# SCH_Tanbre_v2_2026-05-30.net
KiCad netlist of a schematic drawn in EasyEDA
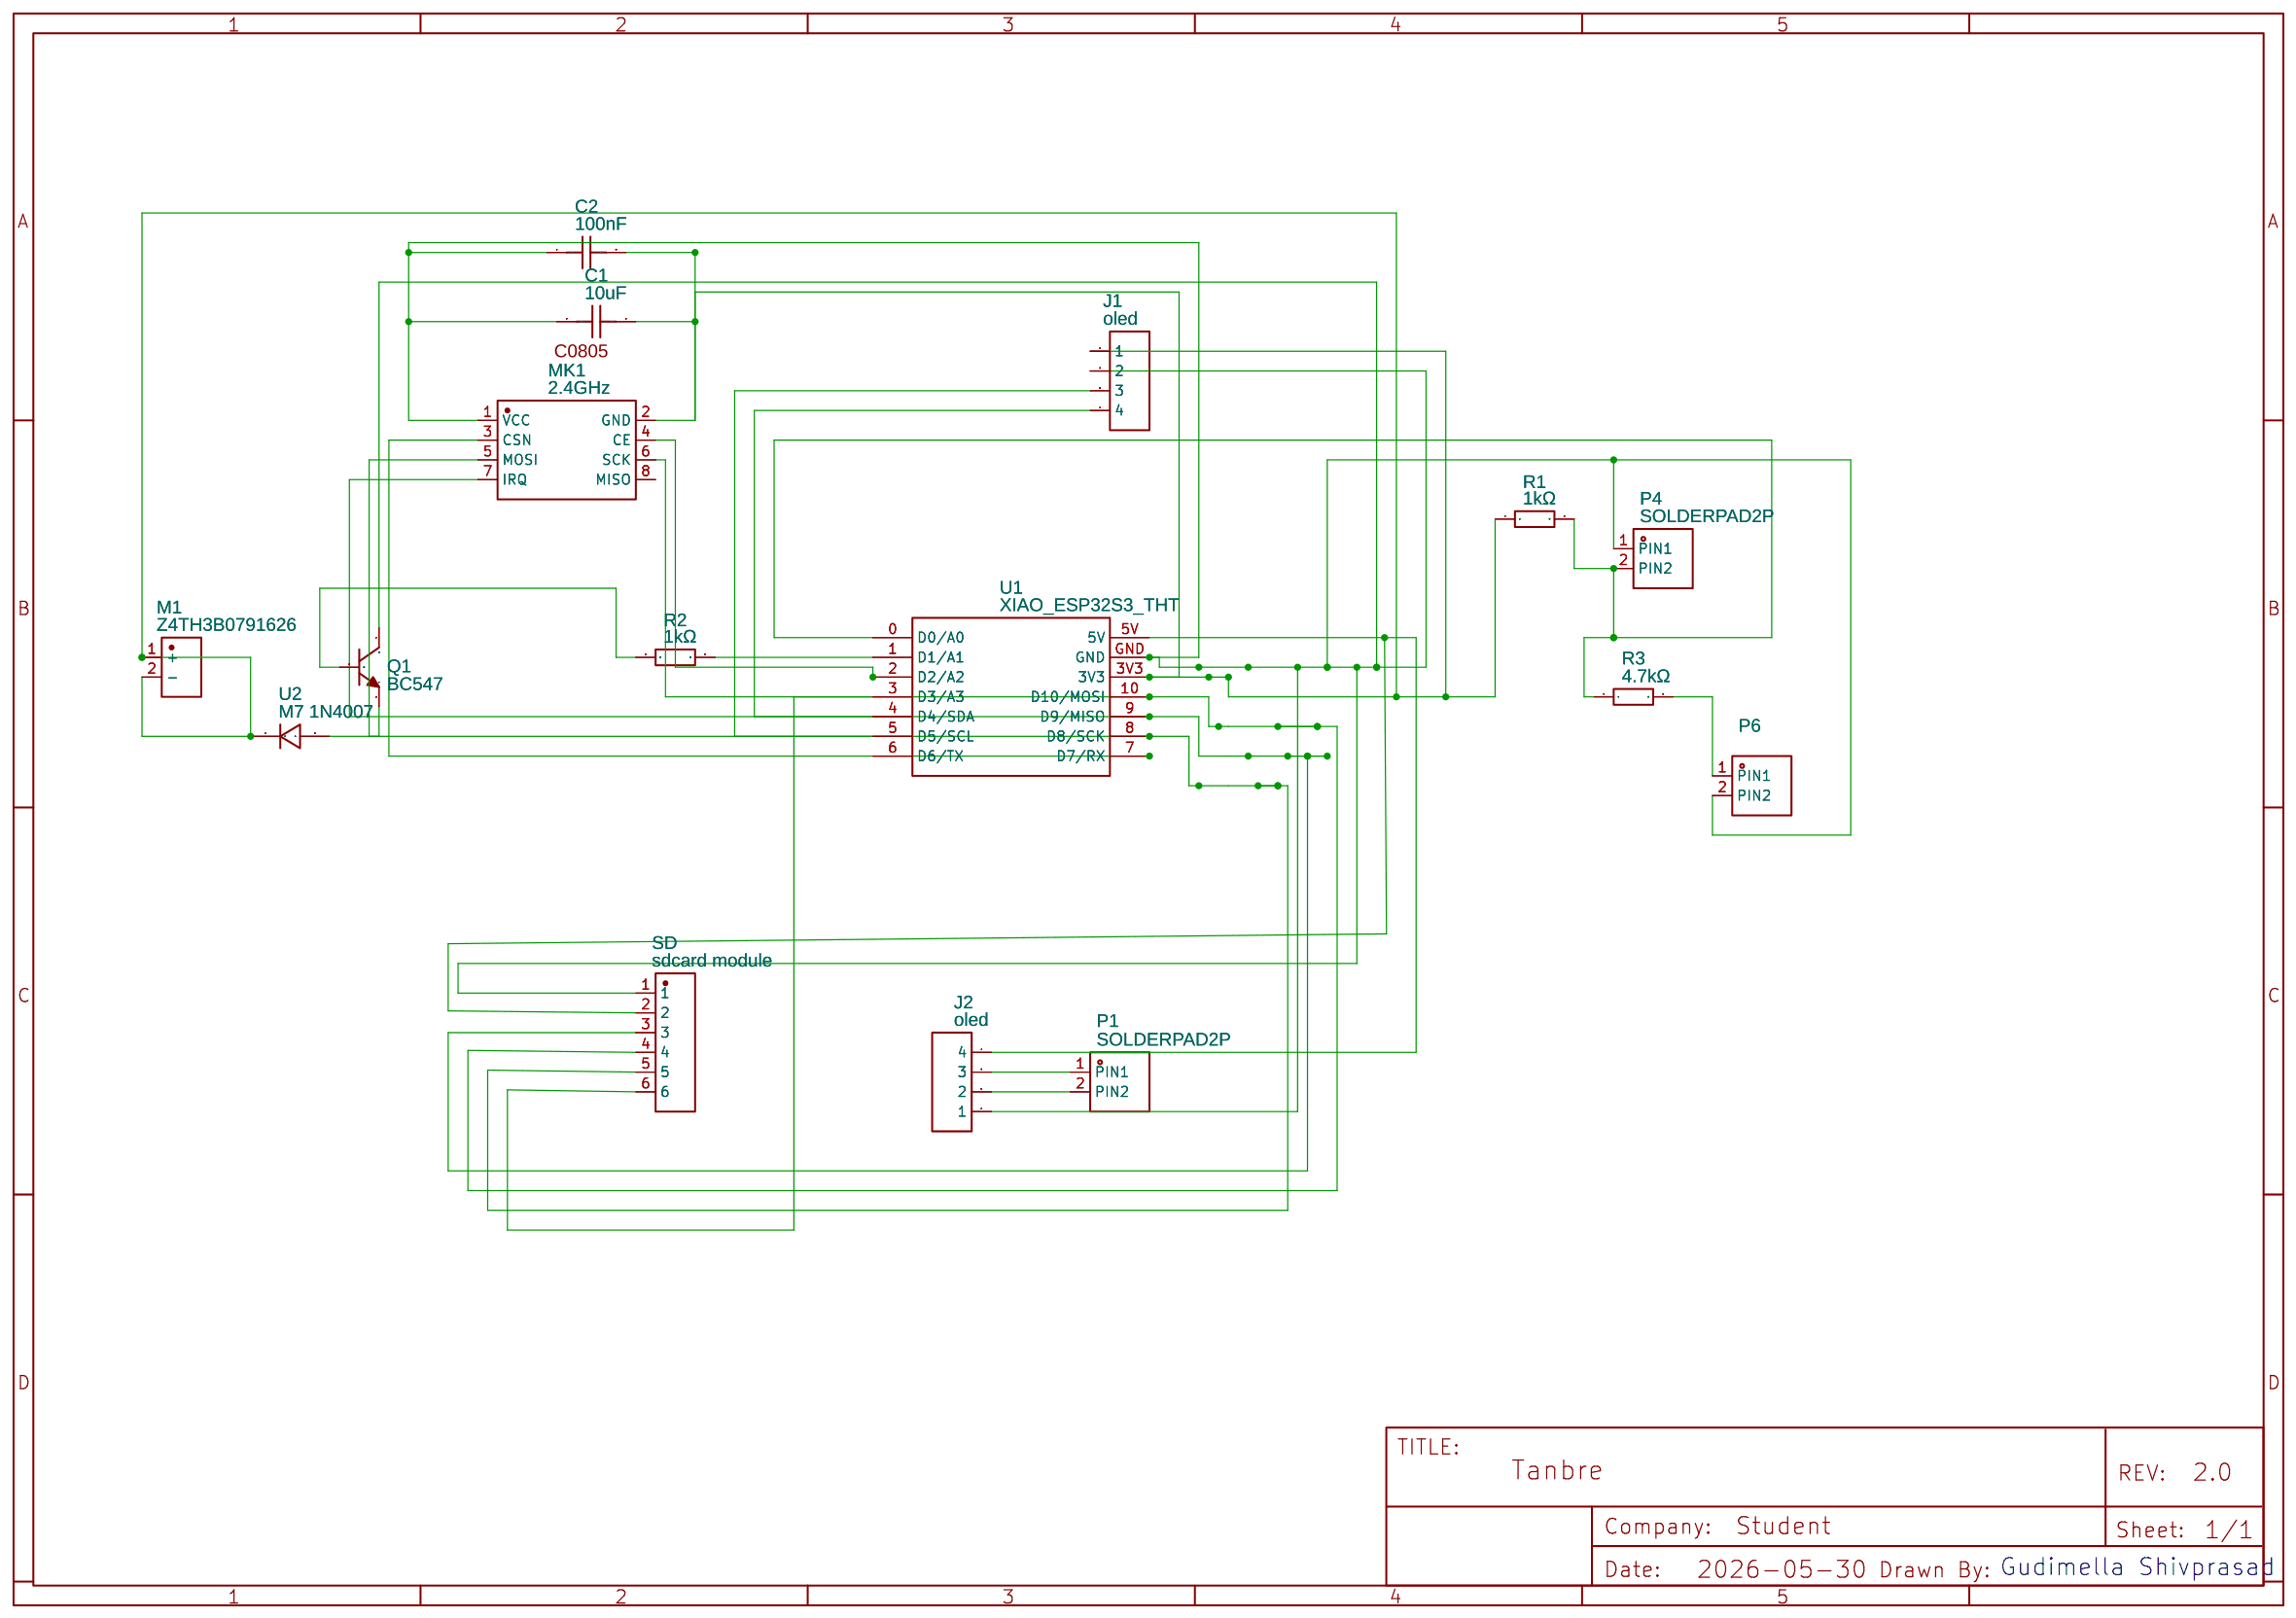
[diagram p0: schematic sheet]

(export (version "E")
  (design (tool "Eeschema 10.0.6"))
  (components
    (comp (ref "C1")
      (value "10uF")
      (fields
        (field (name "Manufacturer Part") "V106K0805X5R250NHP")
        (field (name "Manufacturer") "VIIYONG(微容)")
      )
      (libsource (lib "") (part "V106K0805X5R250NHP"))
    )
    (comp (ref "C2")
      (value "100nF")
      (fields
        (field (name "Manufacturer Part") "VJ0805Y104KXXCW1BC")
        (field (name "Manufacturer") "VISHAY(威世)")
      )
      (libsource (lib "") (part "VJ0805Y104KXXCW1BC"))
    )
    (comp (ref "J1") (value "oled") (libsource (lib "") (part "HDR-M-2.54_1x4_1")))
    (comp (ref "J2") (value "oled") (libsource (lib "") (part "HDR-M-2.54_1x4")))
    (comp (ref "M1")
      (value "Z4TH3B0791626")
      (fields (field (name "Manufacturer") "KOTL(金龙机电)"))
      (libsource (lib "") (part "Z4TH3B0791626"))
    )
    (comp (ref "MK1")
      (value "2.4GHz")
      (fields (field (name "Manufacturer Part") "NF-04") (field (name "Manufacturer") "Ai-Thinker(安信可)"))
      (libsource (lib "") (part "NRF24L01"))
    )
    (comp (ref "P1")
      (value "SOLDERPAD2P")
      (fields (field (name "Manufacturer Part") "New SchematicLib"))
      (libsource (lib "") (part "SOLDERPAD2P"))
    )
    (comp (ref "P4")
      (value "SOLDERPAD2P")
      (fields (field (name "Manufacturer Part") "New SchematicLib"))
      (libsource (lib "") (part "SOLDERPAD2P"))
    )
    (comp (ref "P6")
      (value "SOLDERPAD2P")
      (fields (field (name "Manufacturer Part") "New SchematicLib"))
      (libsource (lib "") (part "SOLDERPAD2P"))
    )
    (comp (ref "Q1")
      (value "BC547")
      (fields
        (field (name "Manufacturer Part") "BC547(RANGE:420-800)")
        (field (name "Manufacturer") "CJ(江苏长电/长晶)")
      )
      (libsource (lib "") (part "BC547"))
    )
    (comp (ref "R1")
      (value "1kΩ")
      (fields (field (name "Manufacturer Part") "CR-02JL6----1K") (field (name "Manufacturer") "Viking(光颉)"))
      (libsource (lib "") (part "CR-02JL6----1K"))
    )
    (comp (ref "R2")
      (value "1kΩ")
      (fields (field (name "Manufacturer Part") "CR-02JL6----1K") (field (name "Manufacturer") "Viking(光颉)"))
      (libsource (lib "") (part "CR-02JL6----1K"))
    )
    (comp (ref "R3")
      (value "4.7kΩ")
      (fields (field (name "Manufacturer Part") "RMC12064.7K5%N") (field (name "Manufacturer") "Tyohm(幸亚电阻)"))
      (libsource (lib "") (part "RMC12064.7K5%N"))
    )
    (comp (ref "SD")
      (value "sdcard module")
      (fields
        (field (name "Manufacturer Part") "HC-PM254-5.0H-1x6PZ")
        (field (name "Manufacturer") "HC(虹成电子)")
      )
      (libsource (lib "") (part "HC-PM254-5.0H-1X6PZ"))
    )
    (comp (ref "U1") (value "XIAO_ESP32S3_THT") (libsource (lib "") (part "XIAO_ESP32S3_THT")))
    (comp (ref "U2")
      (value "M7 1N4007")
      (fields (field (name "Manufacturer") "JUXING(钜兴)"))
      (libsource (lib "") (part "M7 1N4007"))
    )
  )
  (nets
    (net (code "1") (name "Net-(J2-Pad4)") (class "Default")
      (node (ref "J2") (pin "4") (pinfunction "4_4") (pintype "unspecified"))
      (node (ref "SD") (pin "2") (pinfunction "2_2") (pintype "unspecified"))
      (node (ref "U1") (pin "5V") (pinfunction "5V_5V") (pintype "unspecified"))
    )
    (net (code "2") (name "Net-(M1-+)") (class "Default")
      (node (ref "C1") (pin "2") (pinfunction "2_2") (pintype "unspecified"))
      (node (ref "C2") (pin "2") (pinfunction "2_2") (pintype "unspecified"))
      (node (ref "J1") (pin "1") (pinfunction "1_1") (pintype "unspecified"))
      (node (ref "M1") (pin "1") (pinfunction "+_1") (pintype "unspecified"))
      (node (ref "M1") (pin "2") (pinfunction "-_2") (pintype "unspecified"))
      (node (ref "MK1") (pin "2") (pinfunction "GND_2") (pintype "unspecified"))
      (node (ref "R1") (pin "1") (pinfunction "1_1") (pintype "unspecified"))
      (node (ref "U1") (pin "3V3") (pinfunction "3V3_3V3") (pintype "unspecified"))
      (node (ref "U2") (pin "1") (pinfunction "1_1") (pintype "unspecified"))
    )
    (net (code "3") (name "Net-(MK1-CE)") (class "Default")
      (node (ref "MK1") (pin "4") (pinfunction "CE_4") (pintype "unspecified"))
      (node (ref "U1") (pin "2") (pinfunction "D2/A2_2") (pintype "unspecified"))
    )
    (net (code "4") (name "Net-(MK1-CSN)") (class "Default")
      (node (ref "MK1") (pin "3") (pinfunction "CSN_3") (pintype "unspecified"))
      (node (ref "U1") (pin "7") (pinfunction "D7/RX_7") (pintype "unspecified"))
    )
    (net (code "5") (name "Net-(MK1-IRQ)") (class "Default")
      (node (ref "MK1") (pin "7") (pinfunction "IRQ_7") (pintype "unspecified"))
      (node (ref "SD") (pin "3") (pinfunction "3_3") (pintype "unspecified"))
      (node (ref "U1") (pin "9") (pinfunction "D9/MISO_9") (pintype "unspecified"))
    )
    (net (code "6") (name "Net-(MK1-MOSI)") (class "Default")
      (node (ref "MK1") (pin "5") (pinfunction "MOSI_5") (pintype "unspecified"))
      (node (ref "SD") (pin "5") (pinfunction "5_5") (pintype "unspecified"))
      (node (ref "U1") (pin "8") (pinfunction "D8/SCK_8") (pintype "unspecified"))
    )
    (net (code "7") (name "Net-(MK1-SCK)") (class "Default")
      (node (ref "MK1") (pin "6") (pinfunction "SCK_6") (pintype "unspecified"))
      (node (ref "SD") (pin "4") (pinfunction "4_4") (pintype "unspecified"))
      (node (ref "U1") (pin "10") (pinfunction "D10/MOSI_10") (pintype "unspecified"))
    )
    (net (code "8") (name "Net-(MK1-VCC)") (class "Default")
      (node (ref "C1") (pin "1") (pinfunction "1_1") (pintype "unspecified"))
      (node (ref "C2") (pin "1") (pinfunction "1_1") (pintype "unspecified"))
      (node (ref "J1") (pin "2") (pinfunction "2_2") (pintype "unspecified"))
      (node (ref "J2") (pin "1") (pinfunction "1_1") (pintype "unspecified"))
      (node (ref "MK1") (pin "1") (pinfunction "VCC_1") (pintype "unspecified"))
      (node (ref "P4") (pin "1") (pinfunction "PIN1_1") (pintype "unspecified"))
      (node (ref "P6") (pin "2") (pinfunction "PIN2_2") (pintype "unspecified"))
      (node (ref "Q1") (pin "1") (pinfunction "C_1") (pintype "unspecified"))
      (node (ref "SD") (pin "1") (pinfunction "1_1") (pintype "unspecified"))
      (node (ref "U1") (pin "GND") (pinfunction "GND_GND") (pintype "unspecified"))
    )
    (net (code "9") (name "Net-(P1-PIN1)") (class "Default")
      (node (ref "J2") (pin "3") (pinfunction "3_3") (pintype "unspecified"))
      (node (ref "P1") (pin "1") (pinfunction "PIN1_1") (pintype "unspecified"))
    )
    (net (code "10") (name "Net-(P1-PIN2)") (class "Default")
      (node (ref "J2") (pin "2") (pinfunction "2_2") (pintype "unspecified"))
      (node (ref "P1") (pin "2") (pinfunction "PIN2_2") (pintype "unspecified"))
    )
    (net (code "11") (name "Net-(P4-PIN2)") (class "Default")
      (node (ref "P4") (pin "2") (pinfunction "PIN2_2") (pintype "unspecified"))
      (node (ref "R1") (pin "2") (pinfunction "2_2") (pintype "unspecified"))
      (node (ref "R3") (pin "1") (pinfunction "1_1") (pintype "unspecified"))
      (node (ref "U1") (pin "0") (pinfunction "D0/A0_0") (pintype "unspecified"))
    )
    (net (code "12") (name "Net-(P6-PIN1)") (class "Default")
      (node (ref "P6") (pin "1") (pinfunction "PIN1_1") (pintype "unspecified"))
      (node (ref "R3") (pin "2") (pinfunction "2_2") (pintype "unspecified"))
    )
    (net (code "13") (name "Net-(Q1-B)") (class "Default")
      (node (ref "Q1") (pin "2") (pinfunction "B_2") (pintype "unspecified"))
      (node (ref "R2") (pin "1") (pinfunction "1_1") (pintype "unspecified"))
    )
    (net (code "14") (name "Net-(Q1-E)") (class "Default")
      (node (ref "Q1") (pin "3") (pinfunction "E_3") (pintype "unspecified"))
      (node (ref "U2") (pin "2") (pinfunction "2_2") (pintype "unspecified"))
    )
    (net (code "15") (name "Net-(U1-D1{slash}A1)") (class "Default")
      (node (ref "R2") (pin "2") (pinfunction "2_2") (pintype "unspecified"))
      (node (ref "U1") (pin "1") (pinfunction "D1/A1_1") (pintype "unspecified"))
    )
    (net (code "16") (name "Net-(U1-D3{slash}A3)") (class "Default")
      (node (ref "SD") (pin "6") (pinfunction "6_6") (pintype "unspecified"))
      (node (ref "U1") (pin "3") (pinfunction "D3/A3_3") (pintype "unspecified"))
    )
    (net (code "17") (name "Net-(U1-D4{slash}SDA)") (class "Default")
      (node (ref "J1") (pin "4") (pinfunction "4_4") (pintype "unspecified"))
      (node (ref "U1") (pin "4") (pinfunction "D4/SDA_4") (pintype "unspecified"))
    )
    (net (code "18") (name "Net-(U1-D5{slash}SCL)") (class "Default")
      (node (ref "J1") (pin "3") (pinfunction "3_3") (pintype "unspecified"))
      (node (ref "U1") (pin "5") (pinfunction "D5/SCL_5") (pintype "unspecified"))
    )
    (net (code "19") (name "unconnected-(MK1-MISO-Pad8)") (class "Default")
      (node (ref "MK1") (pin "8") (pinfunction "MISO_8") (pintype "unspecified"))
    )
    (net (code "20") (name "unconnected-(U1-D6{slash}TX-Pad6)") (class "Default")
      (node (ref "U1") (pin "6") (pinfunction "D6/TX_6") (pintype "unspecified"))
    )
  )
)
